# SENSOR.net
KiCad netlist of a schematic drawn in Altium Designer
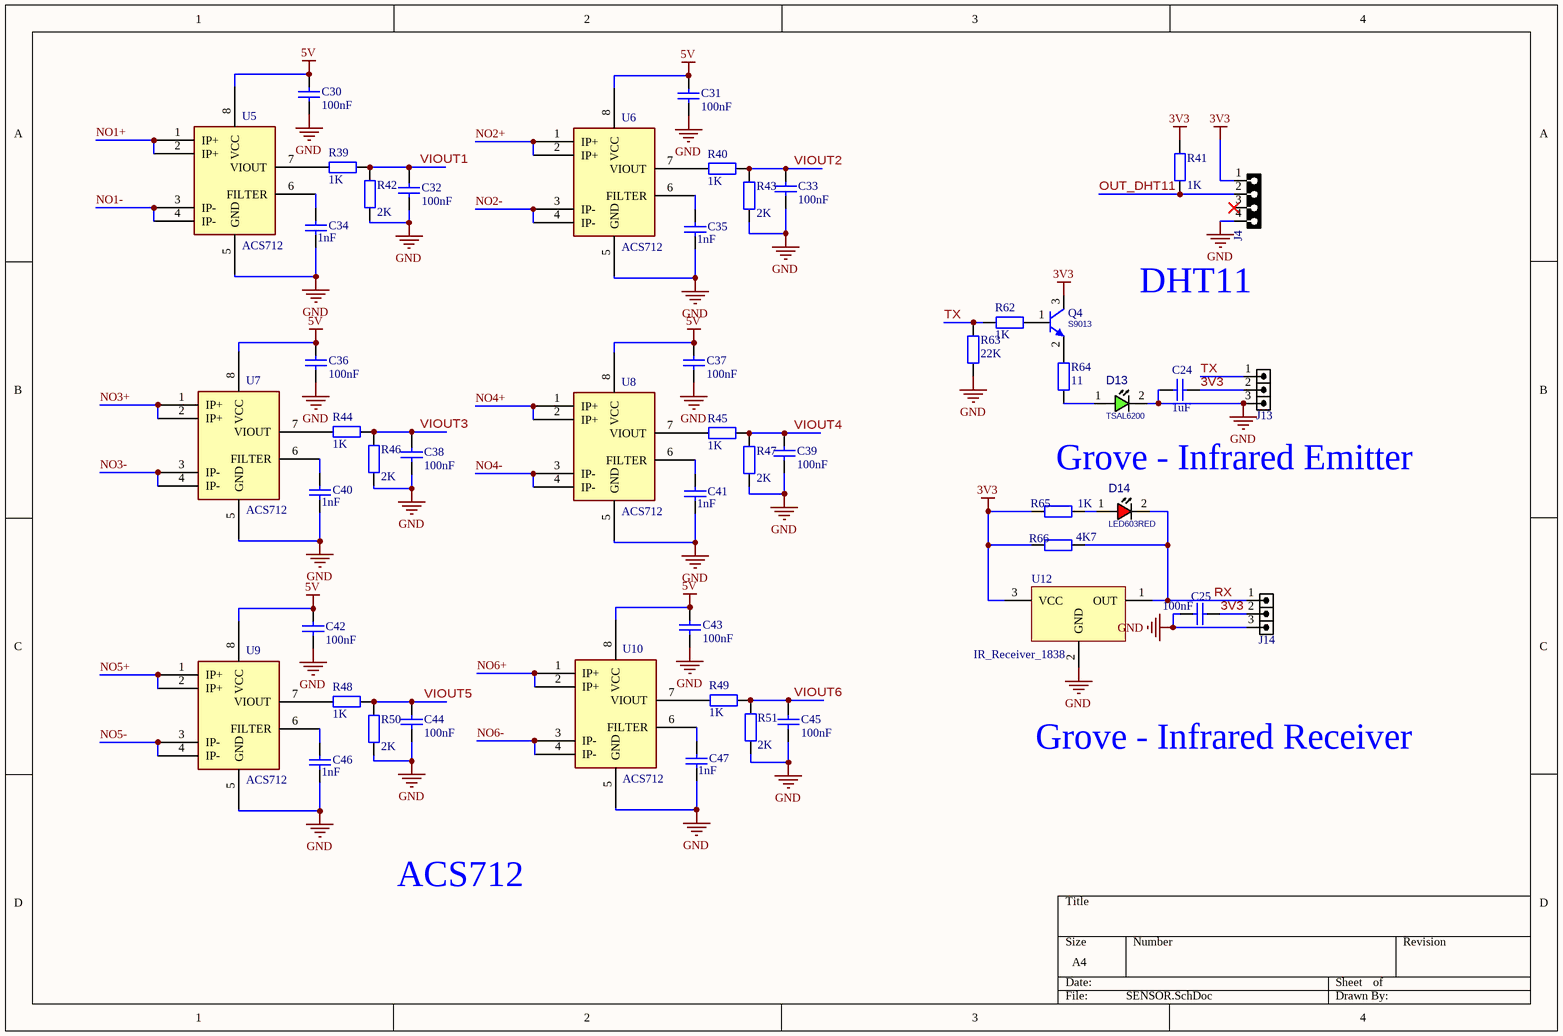
[diagram p0: SENSOR.SchDoc]

(export (version "E")
  (design (tool "Eeschema 10.0.6"))
  (components
    (comp (ref "C24")
      (value "1uF_0603_1%")
      (footprint "tu 0603")
      (description "Capacitor, Ceramic, 50V")
      (fields (field (name "MA_HANG") "1uF"))
      (libsource (lib "THU VIEN SCH") (part "Tu 0603 470pF 50V 10%"))
    )
    (comp (ref "C25")
      (value "100nF_0603_1%")
      (footprint "tu 0603")
      (description "Capacitor, Ceramic, 50V")
      (fields (field (name "MA_HANG") "100nF"))
      (libsource (lib "THU VIEN SCH") (part "Tu 0603 470pF 50V 10%"))
    )
    (comp (ref "C30")
      (value "100nF_0603_1%")
      (footprint "tu 0603")
      (description "Capacitor, Ceramic, 50V")
      (fields (field (name "MA_HANG") "100nF"))
      (libsource (lib "THU VIEN SCH") (part "Tu 0603 470pF 50V 10%"))
    )
    (comp (ref "C31")
      (value "100nF_0603_1%")
      (footprint "tu 0603")
      (description "Capacitor, Ceramic, 50V")
      (fields (field (name "MA_HANG") "100nF"))
      (libsource (lib "THU VIEN SCH") (part "Tu 0603 470pF 50V 10%"))
    )
    (comp (ref "C32")
      (value "100nF_0603_1%")
      (footprint "tu 0603")
      (description "Capacitor, Ceramic, 50V")
      (fields (field (name "MA_HANG") "100nF"))
      (libsource (lib "THU VIEN SCH") (part "Tu 0603 470pF 50V 10%"))
    )
    (comp (ref "C33")
      (value "100nF_0603_1%")
      (footprint "tu 0603")
      (description "Capacitor, Ceramic, 50V")
      (fields (field (name "MA_HANG") "100nF"))
      (libsource (lib "THU VIEN SCH") (part "Tu 0603 470pF 50V 10%"))
    )
    (comp (ref "C34")
      (value "1nF_0603_1%")
      (footprint "tu 0603")
      (description "Capacitor, Ceramic, 50V")
      (fields (field (name "MA_HANG") "1nF"))
      (libsource (lib "THU VIEN SCH") (part "Tu 0603 470pF 50V 10%"))
    )
    (comp (ref "C35")
      (value "1nF_0603_1%")
      (footprint "tu 0603")
      (description "Capacitor, Ceramic, 50V")
      (fields (field (name "MA_HANG") "1nF"))
      (libsource (lib "THU VIEN SCH") (part "Tu 0603 470pF 50V 10%"))
    )
    (comp (ref "C36")
      (value "100nF_0603_1%")
      (footprint "tu 0603")
      (description "Capacitor, Ceramic, 50V")
      (fields (field (name "MA_HANG") "100nF"))
      (libsource (lib "THU VIEN SCH") (part "Tu 0603 470pF 50V 10%"))
    )
    (comp (ref "C37")
      (value "100nF_0603_1%")
      (footprint "tu 0603")
      (description "Capacitor, Ceramic, 50V")
      (fields (field (name "MA_HANG") "100nF"))
      (libsource (lib "THU VIEN SCH") (part "Tu 0603 470pF 50V 10%"))
    )
    (comp (ref "C38")
      (value "100nF_0603_1%")
      (footprint "tu 0603")
      (description "Capacitor, Ceramic, 50V")
      (fields (field (name "MA_HANG") "100nF"))
      (libsource (lib "THU VIEN SCH") (part "Tu 0603 470pF 50V 10%"))
    )
    (comp (ref "C39")
      (value "100nF_0603_1%")
      (footprint "tu 0603")
      (description "Capacitor, Ceramic, 50V")
      (fields (field (name "MA_HANG") "100nF"))
      (libsource (lib "THU VIEN SCH") (part "Tu 0603 470pF 50V 10%"))
    )
    (comp (ref "C40")
      (value "1nF_0603_1%")
      (footprint "tu 0603")
      (description "Capacitor, Ceramic, 50V")
      (fields (field (name "MA_HANG") "1nF"))
      (libsource (lib "THU VIEN SCH") (part "Tu 0603 470pF 50V 10%"))
    )
    (comp (ref "C41")
      (value "1nF_0603_1%")
      (footprint "tu 0603")
      (description "Capacitor, Ceramic, 50V")
      (fields (field (name "MA_HANG") "1nF"))
      (libsource (lib "THU VIEN SCH") (part "Tu 0603 470pF 50V 10%"))
    )
    (comp (ref "C42")
      (value "100nF_0603_1%")
      (footprint "tu 0603")
      (description "Capacitor, Ceramic, 50V")
      (fields (field (name "MA_HANG") "100nF"))
      (libsource (lib "THU VIEN SCH") (part "Tu 0603 470pF 50V 10%"))
    )
    (comp (ref "C43")
      (value "100nF_0603_1%")
      (footprint "tu 0603")
      (description "Capacitor, Ceramic, 50V")
      (fields (field (name "MA_HANG") "100nF"))
      (libsource (lib "THU VIEN SCH") (part "Tu 0603 470pF 50V 10%"))
    )
    (comp (ref "C44")
      (value "100nF_0603_1%")
      (footprint "tu 0603")
      (description "Capacitor, Ceramic, 50V")
      (fields (field (name "MA_HANG") "100nF"))
      (libsource (lib "THU VIEN SCH") (part "Tu 0603 470pF 50V 10%"))
    )
    (comp (ref "C45")
      (value "100nF_0603_1%")
      (footprint "tu 0603")
      (description "Capacitor, Ceramic, 50V")
      (fields (field (name "MA_HANG") "100nF"))
      (libsource (lib "THU VIEN SCH") (part "Tu 0603 470pF 50V 10%"))
    )
    (comp (ref "C46")
      (value "1nF_0603_1%")
      (footprint "tu 0603")
      (description "Capacitor, Ceramic, 50V")
      (fields (field (name "MA_HANG") "1nF"))
      (libsource (lib "THU VIEN SCH") (part "Tu 0603 470pF 50V 10%"))
    )
    (comp (ref "C47")
      (value "1nF_0603_1%")
      (footprint "tu 0603")
      (description "Capacitor, Ceramic, 50V")
      (fields (field (name "MA_HANG") "1nF"))
      (libsource (lib "THU VIEN SCH") (part "Tu 0603 470pF 50V 10%"))
    )
    (comp (ref "D13")
      (value "TSAL6200")
      (footprint "LED3MM")
      (description "LED, THD, 3MM, GREEN")
      (fields (field (name "MANF") "MANF") (field (name "MANF_P#") "MANF_PART#"))
      (libsource (lib "AH_Library") (part "LED_THD_3MM"))
    )
    (comp (ref "D14")
      (value "LED603RED")
      (footprint "LED0603RED")
      (description "LED, SMD, 0603, RED")
      (fields (field (name "MANF") "MANF") (field (name "MANF_P#") "MANF_PART#"))
      (libsource (lib "AH_Library") (part "LED_SMD_0603_RED"))
    )
    (comp (ref "J4")
      (value "HDRF4")
      (footprint "HDR_F_1X4")
      (description "CONN, HEADER, Female, pitch: 2.54mm, 4POS")
      (libsource (lib "AH_Library") (part "HDR_F_1X4"))
    )
    (comp (ref "J13")
      (value "HDRM3")
      (footprint "HDR_M_1X3")
      (description "CONN, HEADER, Male, pitch: 2.54mm, 3POS")
      (libsource (lib "AH_Library") (part "HDR_M_1X3"))
    )
    (comp (ref "J14")
      (value "HDRM3")
      (footprint "HDR_M_1X3")
      (description "CONN, HEADER, Male, pitch: 2.54mm, 3POS")
      (libsource (lib "AH_Library") (part "HDR_M_1X3"))
    )
    (comp (ref "Q4")
      (value "S9013")
      (footprint "SOT23_3")
      (description "BJT, NPN, 25v, 1.5A, SMD, SOT23")
      (fields (field (name "MANF_P#") "SS8050") (field (name "MANF") "GALAXY"))
      (libsource (lib "AH_Library") (part "NPN_SS8050_SOT23"))
    )
    (comp (ref "R39")
      (value "1K_0603_1%")
      (footprint "tro smd 0603")
      (description "RES SMD 0603")
      (fields (field (name "MA_HANG") "1K"))
      (libsource (lib "THU VIEN SCH") (part "Tro 0603 5% 10k"))
    )
    (comp (ref "R40")
      (value "1K_0603_1%")
      (footprint "tro smd 0603")
      (description "RES SMD 0603")
      (fields (field (name "MA_HANG") "1K"))
      (libsource (lib "THU VIEN SCH") (part "Tro 0603 5% 10k"))
    )
    (comp (ref "R41")
      (value "1K_0603_1%")
      (footprint "tro smd 0603")
      (description "RES SMD 0603")
      (fields (field (name "MA_HANG") "1K"))
      (libsource (lib "THU VIEN SCH") (part "Tro 0603 5% 10k"))
    )
    (comp (ref "R42")
      (value "2K_0603_1%")
      (footprint "tro smd 0603")
      (description "RES SMD 0603")
      (fields (field (name "MA_HANG") "2K"))
      (libsource (lib "THU VIEN SCH") (part "Tro 0603 5% 10k"))
    )
    (comp (ref "R43")
      (value "2K_0603_1%")
      (footprint "tro smd 0603")
      (description "RES SMD 0603")
      (fields (field (name "MA_HANG") "2K"))
      (libsource (lib "THU VIEN SCH") (part "Tro 0603 5% 10k"))
    )
    (comp (ref "R44")
      (value "1K_0603_1%")
      (footprint "tro smd 0603")
      (description "RES SMD 0603")
      (fields (field (name "MA_HANG") "1K"))
      (libsource (lib "THU VIEN SCH") (part "Tro 0603 5% 10k"))
    )
    (comp (ref "R45")
      (value "1K_0603_1%")
      (footprint "tro smd 0603")
      (description "RES SMD 0603")
      (fields (field (name "MA_HANG") "1K"))
      (libsource (lib "THU VIEN SCH") (part "Tro 0603 5% 10k"))
    )
    (comp (ref "R46")
      (value "2K_0603_1%")
      (footprint "tro smd 0603")
      (description "RES SMD 0603")
      (fields (field (name "MA_HANG") "2K"))
      (libsource (lib "THU VIEN SCH") (part "Tro 0603 5% 10k"))
    )
    (comp (ref "R47")
      (value "2K_0603_1%")
      (footprint "tro smd 0603")
      (description "RES SMD 0603")
      (fields (field (name "MA_HANG") "2K"))
      (libsource (lib "THU VIEN SCH") (part "Tro 0603 5% 10k"))
    )
    (comp (ref "R48")
      (value "1K_0603_1%")
      (footprint "tro smd 0603")
      (description "RES SMD 0603")
      (fields (field (name "MA_HANG") "1K"))
      (libsource (lib "THU VIEN SCH") (part "Tro 0603 5% 10k"))
    )
    (comp (ref "R49")
      (value "1K_0603_1%")
      (footprint "tro smd 0603")
      (description "RES SMD 0603")
      (fields (field (name "MA_HANG") "1K"))
      (libsource (lib "THU VIEN SCH") (part "Tro 0603 5% 10k"))
    )
    (comp (ref "R50")
      (value "2K_0603_1%")
      (footprint "tro smd 0603")
      (description "RES SMD 0603")
      (fields (field (name "MA_HANG") "2K"))
      (libsource (lib "THU VIEN SCH") (part "Tro 0603 5% 10k"))
    )
    (comp (ref "R51")
      (value "2K_0603_1%")
      (footprint "tro smd 0603")
      (description "RES SMD 0603")
      (fields (field (name "MA_HANG") "2K"))
      (libsource (lib "THU VIEN SCH") (part "Tro 0603 5% 10k"))
    )
    (comp (ref "R62")
      (value "1K_0603_1%")
      (footprint "tro smd 0603")
      (description "RES SMD 0603")
      (fields (field (name "MA_HANG") "1K"))
      (libsource (lib "THU VIEN SCH") (part "Tro 0603 5% 10k"))
    )
    (comp (ref "R63")
      (value "22K_0603_1%")
      (footprint "tro smd 0603")
      (description "RES SMD 0603")
      (fields (field (name "MA_HANG") "22K"))
      (libsource (lib "THU VIEN SCH") (part "Tro 0603 5% 10k"))
    )
    (comp (ref "R64")
      (value "11_0603_1%")
      (footprint "tro smd 0603")
      (description "RES SMD 0603")
      (fields (field (name "MA_HANG") "11"))
      (libsource (lib "THU VIEN SCH") (part "Tro 0603 5% 10k"))
    )
    (comp (ref "R65")
      (value "1K_0603_1%")
      (footprint "tro smd 0603")
      (description "RES SMD 0603")
      (fields (field (name "MA_HANG") "1K"))
      (libsource (lib "THU VIEN SCH") (part "Tro 0603 5% 10k"))
    )
    (comp (ref "R66")
      (value "4K7_0603_1%")
      (footprint "tro smd 0603")
      (description "RES SMD 0603")
      (fields (field (name "MA_HANG") "4K7"))
      (libsource (lib "THU VIEN SCH") (part "Tro 0603 5% 10k"))
    )
    (comp (ref "U5")
      (value "ACS712")
      (footprint "SO_8")
      (description "IC, CURRENT SENSOR, HALL EFFECT")
      (fields (field (name "MANF") "Allegro") (field (name "Comment") "ACS712_8SOIC"))
      (libsource (lib "AH_Library") (part "ACS712"))
    )
    (comp (ref "U6")
      (value "ACS712")
      (footprint "SO_8")
      (description "IC, CURRENT SENSOR, HALL EFFECT")
      (fields (field (name "MANF") "Allegro") (field (name "Comment") "ACS712_8SOIC"))
      (libsource (lib "AH_Library") (part "ACS712"))
    )
    (comp (ref "U7")
      (value "ACS712")
      (footprint "SO_8")
      (description "IC, CURRENT SENSOR, HALL EFFECT")
      (fields (field (name "MANF") "Allegro") (field (name "Comment") "ACS712_8SOIC"))
      (libsource (lib "AH_Library") (part "ACS712"))
    )
    (comp (ref "U8")
      (value "ACS712")
      (footprint "SO_8")
      (description "IC, CURRENT SENSOR, HALL EFFECT")
      (fields (field (name "MANF") "Allegro") (field (name "Comment") "ACS712_8SOIC"))
      (libsource (lib "AH_Library") (part "ACS712"))
    )
    (comp (ref "U9")
      (value "ACS712")
      (footprint "SO_8")
      (description "IC, CURRENT SENSOR, HALL EFFECT")
      (fields (field (name "MANF") "Allegro") (field (name "Comment") "ACS712_8SOIC"))
      (libsource (lib "AH_Library") (part "ACS712"))
    )
    (comp (ref "U10")
      (value "ACS712")
      (footprint "SO_8")
      (description "IC, CURRENT SENSOR, HALL EFFECT")
      (fields (field (name "MANF") "Allegro") (field (name "Comment") "ACS712_8SOIC"))
      (libsource (lib "AH_Library") (part "ACS712"))
    )
    (comp (ref "U12")
      (value "IR_Receiver_1838")
      (footprint "MinhTien_PcbLib:IR_1838")
      (description "1A Regulator")
      (libsource (lib "MinhTien_SCHLib") (part "IR_1838"))
    )
  )
  (nets
    (net (code "1") (name "/NO1+") (class "Default")
      (node (ref "U5") (pin "1") (pinfunction "IP+_1") (pintype "passive"))
      (node (ref "U5") (pin "2") (pinfunction "IP+_2") (pintype "passive"))
    )
    (net (code "2") (name "/NO1-") (class "Default")
      (node (ref "U5") (pin "3") (pinfunction "IP-_3") (pintype "passive"))
      (node (ref "U5") (pin "4") (pinfunction "IP-_4") (pintype "passive"))
    )
    (net (code "3") (name "/NO2+") (class "Default")
      (node (ref "U6") (pin "1") (pinfunction "IP+_1") (pintype "passive"))
      (node (ref "U6") (pin "2") (pinfunction "IP+_2") (pintype "passive"))
    )
    (net (code "4") (name "/NO2-") (class "Default")
      (node (ref "U6") (pin "3") (pinfunction "IP-_3") (pintype "passive"))
      (node (ref "U6") (pin "4") (pinfunction "IP-_4") (pintype "passive"))
    )
    (net (code "5") (name "/NO3+") (class "Default")
      (node (ref "U7") (pin "1") (pinfunction "IP+_1") (pintype "passive"))
      (node (ref "U7") (pin "2") (pinfunction "IP+_2") (pintype "passive"))
    )
    (net (code "6") (name "/NO3-") (class "Default")
      (node (ref "U7") (pin "3") (pinfunction "IP-_3") (pintype "passive"))
      (node (ref "U7") (pin "4") (pinfunction "IP-_4") (pintype "passive"))
    )
    (net (code "7") (name "/NO4+") (class "Default")
      (node (ref "U8") (pin "1") (pinfunction "IP+_1") (pintype "passive"))
      (node (ref "U8") (pin "2") (pinfunction "IP+_2") (pintype "passive"))
    )
    (net (code "8") (name "/NO4-") (class "Default")
      (node (ref "U8") (pin "3") (pinfunction "IP-_3") (pintype "passive"))
      (node (ref "U8") (pin "4") (pinfunction "IP-_4") (pintype "passive"))
    )
    (net (code "9") (name "/NO5+") (class "Default")
      (node (ref "U9") (pin "1") (pinfunction "IP+_1") (pintype "passive"))
      (node (ref "U9") (pin "2") (pinfunction "IP+_2") (pintype "passive"))
    )
    (net (code "10") (name "/NO5-") (class "Default")
      (node (ref "U9") (pin "3") (pinfunction "IP-_3") (pintype "passive"))
      (node (ref "U9") (pin "4") (pinfunction "IP-_4") (pintype "passive"))
    )
    (net (code "11") (name "/NO6+") (class "Default")
      (node (ref "U10") (pin "1") (pinfunction "IP+_1") (pintype "passive"))
      (node (ref "U10") (pin "2") (pinfunction "IP+_2") (pintype "passive"))
    )
    (net (code "12") (name "/NO6-") (class "Default")
      (node (ref "U10") (pin "3") (pinfunction "IP-_3") (pintype "passive"))
      (node (ref "U10") (pin "4") (pinfunction "IP-_4") (pintype "passive"))
    )
    (net (code "13") (name "/OUT_DHT11") (class "Default")
      (node (ref "J4") (pin "2") (pinfunction "2_2") (pintype "passive"))
      (node (ref "R41") (pin "1") (pinfunction "1_1") (pintype "passive"))
    )
    (net (code "14") (name "/RX") (class "Default")
      (node (ref "D14") (pin "2") (pinfunction "CATHODE_2") (pintype "passive"))
      (node (ref "J14") (pin "1") (pinfunction "1_1") (pintype "passive"))
      (node (ref "R66") (pin "1") (pinfunction "1_1") (pintype "passive"))
      (node (ref "U12") (pin "1") (pinfunction "OUT_1") (pintype "passive"))
    )
    (net (code "15") (name "/TX") (class "Default")
      (node (ref "J13") (pin "1") (pinfunction "1_1") (pintype "passive"))
      (node (ref "R62") (pin "1") (pinfunction "1_1") (pintype "passive"))
      (node (ref "R63") (pin "2") (pinfunction "2_2") (pintype "passive"))
    )
    (net (code "16") (name "/VIOUT1") (class "Default")
      (node (ref "C32") (pin "1") (pinfunction "1_1") (pintype "passive"))
      (node (ref "R39") (pin "1") (pinfunction "1_1") (pintype "passive"))
      (node (ref "R42") (pin "2") (pinfunction "2_2") (pintype "passive"))
    )
    (net (code "17") (name "/VIOUT2") (class "Default")
      (node (ref "C33") (pin "1") (pinfunction "1_1") (pintype "passive"))
      (node (ref "R40") (pin "1") (pinfunction "1_1") (pintype "passive"))
      (node (ref "R43") (pin "2") (pinfunction "2_2") (pintype "passive"))
    )
    (net (code "18") (name "/VIOUT3") (class "Default")
      (node (ref "C38") (pin "1") (pinfunction "1_1") (pintype "passive"))
      (node (ref "R44") (pin "1") (pinfunction "1_1") (pintype "passive"))
      (node (ref "R46") (pin "2") (pinfunction "2_2") (pintype "passive"))
    )
    (net (code "19") (name "/VIOUT4") (class "Default")
      (node (ref "C39") (pin "1") (pinfunction "1_1") (pintype "passive"))
      (node (ref "R45") (pin "1") (pinfunction "1_1") (pintype "passive"))
      (node (ref "R47") (pin "2") (pinfunction "2_2") (pintype "passive"))
    )
    (net (code "20") (name "/VIOUT5") (class "Default")
      (node (ref "C44") (pin "1") (pinfunction "1_1") (pintype "passive"))
      (node (ref "R48") (pin "1") (pinfunction "1_1") (pintype "passive"))
      (node (ref "R50") (pin "2") (pinfunction "2_2") (pintype "passive"))
    )
    (net (code "21") (name "/VIOUT6") (class "Default")
      (node (ref "C45") (pin "1") (pinfunction "1_1") (pintype "passive"))
      (node (ref "R49") (pin "1") (pinfunction "1_1") (pintype "passive"))
      (node (ref "R51") (pin "2") (pinfunction "2_2") (pintype "passive"))
    )
    (net (code "22") (name "3V3") (class "Default")
      (node (ref "C24") (pin "2") (pinfunction "2_2") (pintype "passive"))
      (node (ref "C25") (pin "2") (pinfunction "2_2") (pintype "passive"))
      (node (ref "J13") (pin "2") (pinfunction "2_2") (pintype "passive"))
      (node (ref "J14") (pin "2") (pinfunction "2_2") (pintype "passive"))
      (node (ref "J4") (pin "1") (pinfunction "1_1") (pintype "passive"))
      (node (ref "Q4") (pin "3") (pinfunction "C_3") (pintype "passive"))
      (node (ref "R41") (pin "2") (pinfunction "2_2") (pintype "passive"))
      (node (ref "R65") (pin "2") (pinfunction "2_2") (pintype "passive"))
      (node (ref "R66") (pin "2") (pinfunction "2_2") (pintype "passive"))
      (node (ref "U12") (pin "3") (pinfunction "VCC_3") (pintype "power_in"))
    )
    (net (code "23") (name "5V") (class "Default")
      (node (ref "C30") (pin "1") (pinfunction "1_1") (pintype "passive"))
      (node (ref "C31") (pin "1") (pinfunction "1_1") (pintype "passive"))
      (node (ref "C36") (pin "1") (pinfunction "1_1") (pintype "passive"))
      (node (ref "C37") (pin "1") (pinfunction "1_1") (pintype "passive"))
      (node (ref "C42") (pin "1") (pinfunction "1_1") (pintype "passive"))
      (node (ref "C43") (pin "1") (pinfunction "1_1") (pintype "passive"))
      (node (ref "U10") (pin "8") (pinfunction "VCC_8") (pintype "passive"))
      (node (ref "U5") (pin "8") (pinfunction "VCC_8") (pintype "passive"))
      (node (ref "U6") (pin "8") (pinfunction "VCC_8") (pintype "passive"))
      (node (ref "U7") (pin "8") (pinfunction "VCC_8") (pintype "passive"))
      (node (ref "U8") (pin "8") (pinfunction "VCC_8") (pintype "passive"))
      (node (ref "U9") (pin "8") (pinfunction "VCC_8") (pintype "passive"))
    )
    (net (code "24") (name "GND") (class "Default")
      (node (ref "C24") (pin "1") (pinfunction "1_1") (pintype "passive"))
      (node (ref "C25") (pin "1") (pinfunction "1_1") (pintype "passive"))
      (node (ref "C30") (pin "2") (pinfunction "2_2") (pintype "passive"))
      (node (ref "C31") (pin "2") (pinfunction "2_2") (pintype "passive"))
      (node (ref "C32") (pin "2") (pinfunction "2_2") (pintype "passive"))
      (node (ref "C33") (pin "2") (pinfunction "2_2") (pintype "passive"))
      (node (ref "C34") (pin "2") (pinfunction "2_2") (pintype "passive"))
      (node (ref "C35") (pin "2") (pinfunction "2_2") (pintype "passive"))
      (node (ref "C36") (pin "2") (pinfunction "2_2") (pintype "passive"))
      (node (ref "C37") (pin "2") (pinfunction "2_2") (pintype "passive"))
      (node (ref "C38") (pin "2") (pinfunction "2_2") (pintype "passive"))
      (node (ref "C39") (pin "2") (pinfunction "2_2") (pintype "passive"))
      (node (ref "C40") (pin "2") (pinfunction "2_2") (pintype "passive"))
      (node (ref "C41") (pin "2") (pinfunction "2_2") (pintype "passive"))
      (node (ref "C42") (pin "2") (pinfunction "2_2") (pintype "passive"))
      (node (ref "C43") (pin "2") (pinfunction "2_2") (pintype "passive"))
      (node (ref "C44") (pin "2") (pinfunction "2_2") (pintype "passive"))
      (node (ref "C45") (pin "2") (pinfunction "2_2") (pintype "passive"))
      (node (ref "C46") (pin "2") (pinfunction "2_2") (pintype "passive"))
      (node (ref "C47") (pin "2") (pinfunction "2_2") (pintype "passive"))
      (node (ref "D13") (pin "2") (pinfunction "CATHODE_2") (pintype "passive"))
      (node (ref "J13") (pin "3") (pinfunction "3_3") (pintype "passive"))
      (node (ref "J14") (pin "3") (pinfunction "3_3") (pintype "passive"))
      (node (ref "J4") (pin "4") (pinfunction "4_4") (pintype "passive"))
      (node (ref "R42") (pin "1") (pinfunction "1_1") (pintype "passive"))
      (node (ref "R43") (pin "1") (pinfunction "1_1") (pintype "passive"))
      (node (ref "R46") (pin "1") (pinfunction "1_1") (pintype "passive"))
      (node (ref "R47") (pin "1") (pinfunction "1_1") (pintype "passive"))
      (node (ref "R50") (pin "1") (pinfunction "1_1") (pintype "passive"))
      (node (ref "R51") (pin "1") (pinfunction "1_1") (pintype "passive"))
      (node (ref "R63") (pin "1") (pinfunction "1_1") (pintype "passive"))
      (node (ref "U10") (pin "5") (pinfunction "GND_5") (pintype "passive"))
      (node (ref "U12") (pin "2") (pinfunction "GND_2") (pintype "power_in"))
      (node (ref "U5") (pin "5") (pinfunction "GND_5") (pintype "passive"))
      (node (ref "U6") (pin "5") (pinfunction "GND_5") (pintype "passive"))
      (node (ref "U7") (pin "5") (pinfunction "GND_5") (pintype "passive"))
      (node (ref "U8") (pin "5") (pinfunction "GND_5") (pintype "passive"))
      (node (ref "U9") (pin "5") (pinfunction "GND_5") (pintype "passive"))
    )
    (net (code "25") (name "Net-(D13-ANODE)") (class "Default")
      (node (ref "D13") (pin "1") (pinfunction "ANODE_1") (pintype "passive"))
      (node (ref "R64") (pin "2") (pinfunction "2_2") (pintype "passive"))
    )
    (net (code "26") (name "Net-(D14-ANODE)") (class "Default")
      (node (ref "D14") (pin "1") (pinfunction "ANODE_1") (pintype "passive"))
      (node (ref "R65") (pin "1") (pinfunction "1_1") (pintype "passive"))
    )
    (net (code "27") (name "Net-(Q4-B)") (class "Default")
      (node (ref "Q4") (pin "1") (pinfunction "B_1") (pintype "passive"))
      (node (ref "R62") (pin "2") (pinfunction "2_2") (pintype "passive"))
    )
    (net (code "28") (name "Net-(Q4-E)") (class "Default")
      (node (ref "Q4") (pin "2") (pinfunction "E_2") (pintype "passive"))
      (node (ref "R64") (pin "1") (pinfunction "1_1") (pintype "passive"))
    )
    (net (code "29") (name "Net-(U5-FILTER)") (class "Default")
      (node (ref "C34") (pin "1") (pinfunction "1_1") (pintype "passive"))
      (node (ref "U5") (pin "6") (pinfunction "FILTER_6") (pintype "passive"))
    )
    (net (code "30") (name "Net-(U5-VIOUT)") (class "Default")
      (node (ref "R39") (pin "2") (pinfunction "2_2") (pintype "passive"))
      (node (ref "U5") (pin "7") (pinfunction "VIOUT_7") (pintype "passive"))
    )
    (net (code "31") (name "Net-(U6-FILTER)") (class "Default")
      (node (ref "C35") (pin "1") (pinfunction "1_1") (pintype "passive"))
      (node (ref "U6") (pin "6") (pinfunction "FILTER_6") (pintype "passive"))
    )
    (net (code "32") (name "Net-(U6-VIOUT)") (class "Default")
      (node (ref "R40") (pin "2") (pinfunction "2_2") (pintype "passive"))
      (node (ref "U6") (pin "7") (pinfunction "VIOUT_7") (pintype "passive"))
    )
    (net (code "33") (name "Net-(U7-FILTER)") (class "Default")
      (node (ref "C40") (pin "1") (pinfunction "1_1") (pintype "passive"))
      (node (ref "U7") (pin "6") (pinfunction "FILTER_6") (pintype "passive"))
    )
    (net (code "34") (name "Net-(U7-VIOUT)") (class "Default")
      (node (ref "R44") (pin "2") (pinfunction "2_2") (pintype "passive"))
      (node (ref "U7") (pin "7") (pinfunction "VIOUT_7") (pintype "passive"))
    )
    (net (code "35") (name "Net-(U8-FILTER)") (class "Default")
      (node (ref "C41") (pin "1") (pinfunction "1_1") (pintype "passive"))
      (node (ref "U8") (pin "6") (pinfunction "FILTER_6") (pintype "passive"))
    )
    (net (code "36") (name "Net-(U8-VIOUT)") (class "Default")
      (node (ref "R45") (pin "2") (pinfunction "2_2") (pintype "passive"))
      (node (ref "U8") (pin "7") (pinfunction "VIOUT_7") (pintype "passive"))
    )
    (net (code "37") (name "Net-(U9-FILTER)") (class "Default")
      (node (ref "C46") (pin "1") (pinfunction "1_1") (pintype "passive"))
      (node (ref "U9") (pin "6") (pinfunction "FILTER_6") (pintype "passive"))
    )
    (net (code "38") (name "Net-(U9-VIOUT)") (class "Default")
      (node (ref "R48") (pin "2") (pinfunction "2_2") (pintype "passive"))
      (node (ref "U9") (pin "7") (pinfunction "VIOUT_7") (pintype "passive"))
    )
    (net (code "39") (name "Net-(U10-FILTER)") (class "Default")
      (node (ref "C47") (pin "1") (pinfunction "1_1") (pintype "passive"))
      (node (ref "U10") (pin "6") (pinfunction "FILTER_6") (pintype "passive"))
    )
    (net (code "40") (name "Net-(U10-VIOUT)") (class "Default")
      (node (ref "R49") (pin "2") (pinfunction "2_2") (pintype "passive"))
      (node (ref "U10") (pin "7") (pinfunction "VIOUT_7") (pintype "passive"))
    )
    (net (code "41") (name "unconnected-(J4-Pad3)") (class "Default")
      (node (ref "J4") (pin "3") (pinfunction "3_3") (pintype "passive+no_connect"))
    )
  )
)
